# tappytap.net
KiCad netlist of a schematic drawn in EAGLE
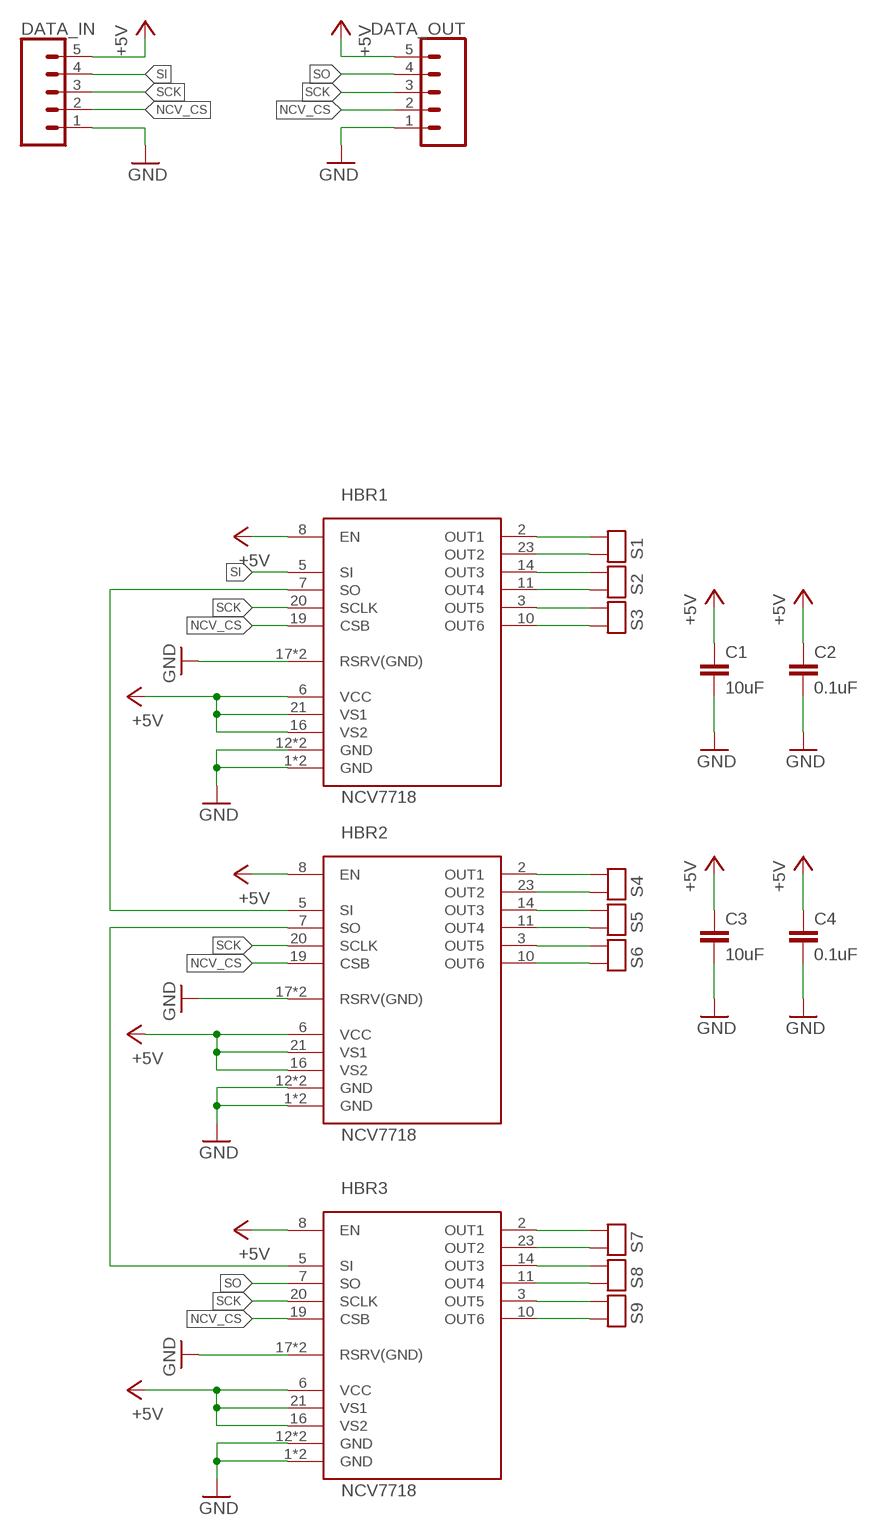
[diagram p0: schematic, sheet 1]

(export (version "E")
  (design (tool "Eeschema 10.0.6"))
  (components
    (comp (ref "C1")
      (value "10uF")
      (footprint "eagle-import:C0603")
      (libsource (lib "eagle-import") (part "C-EUC0603"))
    )
    (comp (ref "C2")
      (value "0.1uF")
      (footprint "eagle-import:C0603")
      (libsource (lib "eagle-import") (part "C-EUC0603"))
    )
    (comp (ref "C3")
      (value "10uF")
      (footprint "eagle-import:C0603")
      (libsource (lib "eagle-import") (part "C-EUC0603"))
    )
    (comp (ref "C4")
      (value "0.1uF")
      (footprint "eagle-import:C0603")
      (libsource (lib "eagle-import") (part "C-EUC0603"))
    )
    (comp (ref "DATA_IN")
      (value "CONN_05")
      (footprint "eagle-import:1X05")
      (libsource (lib "eagle-import") (part "CONN_05"))
    )
    (comp (ref "DATA_OUT")
      (value "CONN_05")
      (footprint "eagle-import:1X05")
      (libsource (lib "eagle-import") (part "CONN_05"))
    )
    (comp (ref "HBR1")
      (value "NCV7718")
      (footprint "eagle-import:SSOP-24")
      (libsource (lib "eagle-import") (part "NCV7718"))
    )
    (comp (ref "HBR2")
      (value "NCV7718")
      (footprint "eagle-import:SSOP-24")
      (libsource (lib "eagle-import") (part "NCV7718"))
    )
    (comp (ref "HBR3")
      (value "NCV7718")
      (footprint "eagle-import:SSOP-24")
      (libsource (lib "eagle-import") (part "NCV7718"))
    )
    (comp (ref "S1")
      (value "TP2")
      (footprint "eagle-import:TP2_2MM")
      (libsource (lib "eagle-import") (part "TP2"))
    )
    (comp (ref "S2")
      (value "TP2")
      (footprint "eagle-import:TP2_2MM")
      (libsource (lib "eagle-import") (part "TP2"))
    )
    (comp (ref "S3")
      (value "TP2")
      (footprint "eagle-import:TP2_2MM")
      (libsource (lib "eagle-import") (part "TP2"))
    )
    (comp (ref "S4")
      (value "TP2")
      (footprint "eagle-import:TP2_2MM")
      (libsource (lib "eagle-import") (part "TP2"))
    )
    (comp (ref "S5")
      (value "TP2")
      (footprint "eagle-import:TP2_2MM")
      (libsource (lib "eagle-import") (part "TP2"))
    )
    (comp (ref "S6")
      (value "TP2")
      (footprint "eagle-import:TP2_2MM")
      (libsource (lib "eagle-import") (part "TP2"))
    )
    (comp (ref "S7")
      (value "TP2")
      (footprint "eagle-import:TP2_2MM")
      (libsource (lib "eagle-import") (part "TP2"))
    )
    (comp (ref "S8")
      (value "TP2")
      (footprint "eagle-import:TP2_2MM")
      (libsource (lib "eagle-import") (part "TP2"))
    )
    (comp (ref "S9")
      (value "TP2")
      (footprint "eagle-import:TP2_2MM")
      (libsource (lib "eagle-import") (part "TP2"))
    )
  )
  (nets
    (net (code "1") (name "+5V") (class "Default")
      (node (ref "C1") (pin "1") (pinfunction "1_1") (pintype "passive"))
      (node (ref "C2") (pin "1") (pinfunction "1_1") (pintype "passive"))
      (node (ref "C3") (pin "1") (pinfunction "1_1") (pintype "passive"))
      (node (ref "C4") (pin "1") (pinfunction "1_1") (pintype "passive"))
      (node (ref "DATA_IN") (pin "5") (pinfunction "5_5") (pintype "passive"))
      (node (ref "DATA_OUT") (pin "5") (pinfunction "5_5") (pintype "passive"))
      (node (ref "HBR1") (pin "16") (pinfunction "VS2_16") (pintype "bidirectional"))
      (node (ref "HBR1") (pin "21") (pinfunction "VS1_21") (pintype "bidirectional"))
      (node (ref "HBR1") (pin "6") (pinfunction "VCC_6") (pintype "bidirectional"))
      (node (ref "HBR1") (pin "8") (pinfunction "EN_8") (pintype "bidirectional"))
      (node (ref "HBR2") (pin "16") (pinfunction "VS2_16") (pintype "bidirectional"))
      (node (ref "HBR2") (pin "21") (pinfunction "VS1_21") (pintype "bidirectional"))
      (node (ref "HBR2") (pin "6") (pinfunction "VCC_6") (pintype "bidirectional"))
      (node (ref "HBR2") (pin "8") (pinfunction "EN_8") (pintype "bidirectional"))
      (node (ref "HBR3") (pin "16") (pinfunction "VS2_16") (pintype "bidirectional"))
      (node (ref "HBR3") (pin "21") (pinfunction "VS1_21") (pintype "bidirectional"))
      (node (ref "HBR3") (pin "6") (pinfunction "VCC_6") (pintype "bidirectional"))
      (node (ref "HBR3") (pin "8") (pinfunction "EN_8") (pintype "bidirectional"))
    )
    (net (code "2") (name "GND") (class "Default")
      (node (ref "C1") (pin "2") (pinfunction "2_2") (pintype "passive"))
      (node (ref "C2") (pin "2") (pinfunction "2_2") (pintype "passive"))
      (node (ref "C3") (pin "2") (pinfunction "2_2") (pintype "passive"))
      (node (ref "C4") (pin "2") (pinfunction "2_2") (pintype "passive"))
      (node (ref "DATA_IN") (pin "1") (pinfunction "1_1") (pintype "passive"))
      (node (ref "DATA_OUT") (pin "1") (pinfunction "1_1") (pintype "passive"))
      (node (ref "HBR1") (pin "1") (pinfunction "GND_1") (pintype "bidirectional"))
      (node (ref "HBR1") (pin "12") (pinfunction "GND_12") (pintype "bidirectional"))
      (node (ref "HBR1") (pin "13") (pinfunction "GND_13") (pintype "bidirectional"))
      (node (ref "HBR1") (pin "17") (pinfunction "RSRV(GND)_17") (pintype "bidirectional"))
      (node (ref "HBR1") (pin "18") (pinfunction "RSRV(GND)_18") (pintype "bidirectional"))
      (node (ref "HBR1") (pin "24") (pinfunction "GND_24") (pintype "bidirectional"))
      (node (ref "HBR2") (pin "1") (pinfunction "GND_1") (pintype "bidirectional"))
      (node (ref "HBR2") (pin "12") (pinfunction "GND_12") (pintype "bidirectional"))
      (node (ref "HBR2") (pin "13") (pinfunction "GND_13") (pintype "bidirectional"))
      (node (ref "HBR2") (pin "17") (pinfunction "RSRV(GND)_17") (pintype "bidirectional"))
      (node (ref "HBR2") (pin "18") (pinfunction "RSRV(GND)_18") (pintype "bidirectional"))
      (node (ref "HBR2") (pin "24") (pinfunction "GND_24") (pintype "bidirectional"))
      (node (ref "HBR3") (pin "1") (pinfunction "GND_1") (pintype "bidirectional"))
      (node (ref "HBR3") (pin "12") (pinfunction "GND_12") (pintype "bidirectional"))
      (node (ref "HBR3") (pin "13") (pinfunction "GND_13") (pintype "bidirectional"))
      (node (ref "HBR3") (pin "17") (pinfunction "RSRV(GND)_17") (pintype "bidirectional"))
      (node (ref "HBR3") (pin "18") (pinfunction "RSRV(GND)_18") (pintype "bidirectional"))
      (node (ref "HBR3") (pin "24") (pinfunction "GND_24") (pintype "bidirectional"))
    )
    (net (code "3") (name "NCV_CS") (class "Default")
      (node (ref "DATA_IN") (pin "2") (pinfunction "2_2") (pintype "passive"))
      (node (ref "DATA_OUT") (pin "2") (pinfunction "2_2") (pintype "passive"))
      (node (ref "HBR1") (pin "19") (pinfunction "CSB_19") (pintype "bidirectional"))
      (node (ref "HBR2") (pin "19") (pinfunction "CSB_19") (pintype "bidirectional"))
      (node (ref "HBR3") (pin "19") (pinfunction "CSB_19") (pintype "bidirectional"))
    )
    (net (code "4") (name "Net-(HBR1-OUT1)") (class "Default")
      (node (ref "HBR1") (pin "2") (pinfunction "OUT1_2") (pintype "bidirectional"))
      (node (ref "S1") (pin "P$1") (pinfunction "0_P$1") (pintype "bidirectional"))
    )
    (net (code "5") (name "Net-(HBR1-OUT2)") (class "Default")
      (node (ref "HBR1") (pin "23") (pinfunction "OUT2_23") (pintype "bidirectional"))
      (node (ref "S1") (pin "P$2") (pinfunction "1_P$2") (pintype "bidirectional"))
    )
    (net (code "6") (name "Net-(HBR1-OUT3)") (class "Default")
      (node (ref "HBR1") (pin "14") (pinfunction "OUT3_14") (pintype "bidirectional"))
      (node (ref "S2") (pin "P$1") (pinfunction "0_P$1") (pintype "bidirectional"))
    )
    (net (code "7") (name "Net-(HBR1-OUT4)") (class "Default")
      (node (ref "HBR1") (pin "11") (pinfunction "OUT4_11") (pintype "bidirectional"))
      (node (ref "S2") (pin "P$2") (pinfunction "1_P$2") (pintype "bidirectional"))
    )
    (net (code "8") (name "Net-(HBR1-OUT5)") (class "Default")
      (node (ref "HBR1") (pin "3") (pinfunction "OUT5_3") (pintype "bidirectional"))
      (node (ref "S3") (pin "P$1") (pinfunction "0_P$1") (pintype "bidirectional"))
    )
    (net (code "9") (name "Net-(HBR1-OUT6)") (class "Default")
      (node (ref "HBR1") (pin "10") (pinfunction "OUT6_10") (pintype "bidirectional"))
      (node (ref "S3") (pin "P$2") (pinfunction "1_P$2") (pintype "bidirectional"))
    )
    (net (code "10") (name "Net-(HBR1-SO)") (class "Default")
      (node (ref "HBR1") (pin "7") (pinfunction "SO_7") (pintype "bidirectional"))
      (node (ref "HBR2") (pin "5") (pinfunction "SI_5") (pintype "bidirectional"))
    )
    (net (code "11") (name "Net-(HBR2-OUT1)") (class "Default")
      (node (ref "HBR2") (pin "2") (pinfunction "OUT1_2") (pintype "bidirectional"))
      (node (ref "S4") (pin "P$1") (pinfunction "0_P$1") (pintype "bidirectional"))
    )
    (net (code "12") (name "Net-(HBR2-OUT2)") (class "Default")
      (node (ref "HBR2") (pin "23") (pinfunction "OUT2_23") (pintype "bidirectional"))
      (node (ref "S4") (pin "P$2") (pinfunction "1_P$2") (pintype "bidirectional"))
    )
    (net (code "13") (name "Net-(HBR2-OUT3)") (class "Default")
      (node (ref "HBR2") (pin "14") (pinfunction "OUT3_14") (pintype "bidirectional"))
      (node (ref "S5") (pin "P$1") (pinfunction "0_P$1") (pintype "bidirectional"))
    )
    (net (code "14") (name "Net-(HBR2-OUT4)") (class "Default")
      (node (ref "HBR2") (pin "11") (pinfunction "OUT4_11") (pintype "bidirectional"))
      (node (ref "S5") (pin "P$2") (pinfunction "1_P$2") (pintype "bidirectional"))
    )
    (net (code "15") (name "Net-(HBR2-OUT5)") (class "Default")
      (node (ref "HBR2") (pin "3") (pinfunction "OUT5_3") (pintype "bidirectional"))
      (node (ref "S6") (pin "P$1") (pinfunction "0_P$1") (pintype "bidirectional"))
    )
    (net (code "16") (name "Net-(HBR2-OUT6)") (class "Default")
      (node (ref "HBR2") (pin "10") (pinfunction "OUT6_10") (pintype "bidirectional"))
      (node (ref "S6") (pin "P$2") (pinfunction "1_P$2") (pintype "bidirectional"))
    )
    (net (code "17") (name "Net-(HBR2-SO)") (class "Default")
      (node (ref "HBR2") (pin "7") (pinfunction "SO_7") (pintype "bidirectional"))
      (node (ref "HBR3") (pin "5") (pinfunction "SI_5") (pintype "bidirectional"))
    )
    (net (code "18") (name "Net-(HBR3-OUT1)") (class "Default")
      (node (ref "HBR3") (pin "2") (pinfunction "OUT1_2") (pintype "bidirectional"))
      (node (ref "S7") (pin "P$1") (pinfunction "0_P$1") (pintype "bidirectional"))
    )
    (net (code "19") (name "Net-(HBR3-OUT2)") (class "Default")
      (node (ref "HBR3") (pin "23") (pinfunction "OUT2_23") (pintype "bidirectional"))
      (node (ref "S7") (pin "P$2") (pinfunction "1_P$2") (pintype "bidirectional"))
    )
    (net (code "20") (name "Net-(HBR3-OUT3)") (class "Default")
      (node (ref "HBR3") (pin "14") (pinfunction "OUT3_14") (pintype "bidirectional"))
      (node (ref "S8") (pin "P$1") (pinfunction "0_P$1") (pintype "bidirectional"))
    )
    (net (code "21") (name "Net-(HBR3-OUT4)") (class "Default")
      (node (ref "HBR3") (pin "11") (pinfunction "OUT4_11") (pintype "bidirectional"))
      (node (ref "S8") (pin "P$2") (pinfunction "1_P$2") (pintype "bidirectional"))
    )
    (net (code "22") (name "Net-(HBR3-OUT5)") (class "Default")
      (node (ref "HBR3") (pin "3") (pinfunction "OUT5_3") (pintype "bidirectional"))
      (node (ref "S9") (pin "P$1") (pinfunction "0_P$1") (pintype "bidirectional"))
    )
    (net (code "23") (name "Net-(HBR3-OUT6)") (class "Default")
      (node (ref "HBR3") (pin "10") (pinfunction "OUT6_10") (pintype "bidirectional"))
      (node (ref "S9") (pin "P$2") (pinfunction "1_P$2") (pintype "bidirectional"))
    )
    (net (code "24") (name "SCK") (class "Default")
      (node (ref "DATA_IN") (pin "3") (pinfunction "3_3") (pintype "passive"))
      (node (ref "DATA_OUT") (pin "3") (pinfunction "3_3") (pintype "passive"))
      (node (ref "HBR1") (pin "20") (pinfunction "SCLK_20") (pintype "bidirectional"))
      (node (ref "HBR2") (pin "20") (pinfunction "SCLK_20") (pintype "bidirectional"))
      (node (ref "HBR3") (pin "20") (pinfunction "SCLK_20") (pintype "bidirectional"))
    )
    (net (code "25") (name "SI") (class "Default")
      (node (ref "DATA_IN") (pin "4") (pinfunction "4_4") (pintype "passive"))
      (node (ref "HBR1") (pin "5") (pinfunction "SI_5") (pintype "bidirectional"))
    )
    (net (code "26") (name "SO") (class "Default")
      (node (ref "DATA_OUT") (pin "4") (pinfunction "4_4") (pintype "passive"))
      (node (ref "HBR3") (pin "7") (pinfunction "SO_7") (pintype "bidirectional"))
    )
  )
)
